# Sheet_Power.net
KiCad netlist of a schematic drawn in Altium Designer
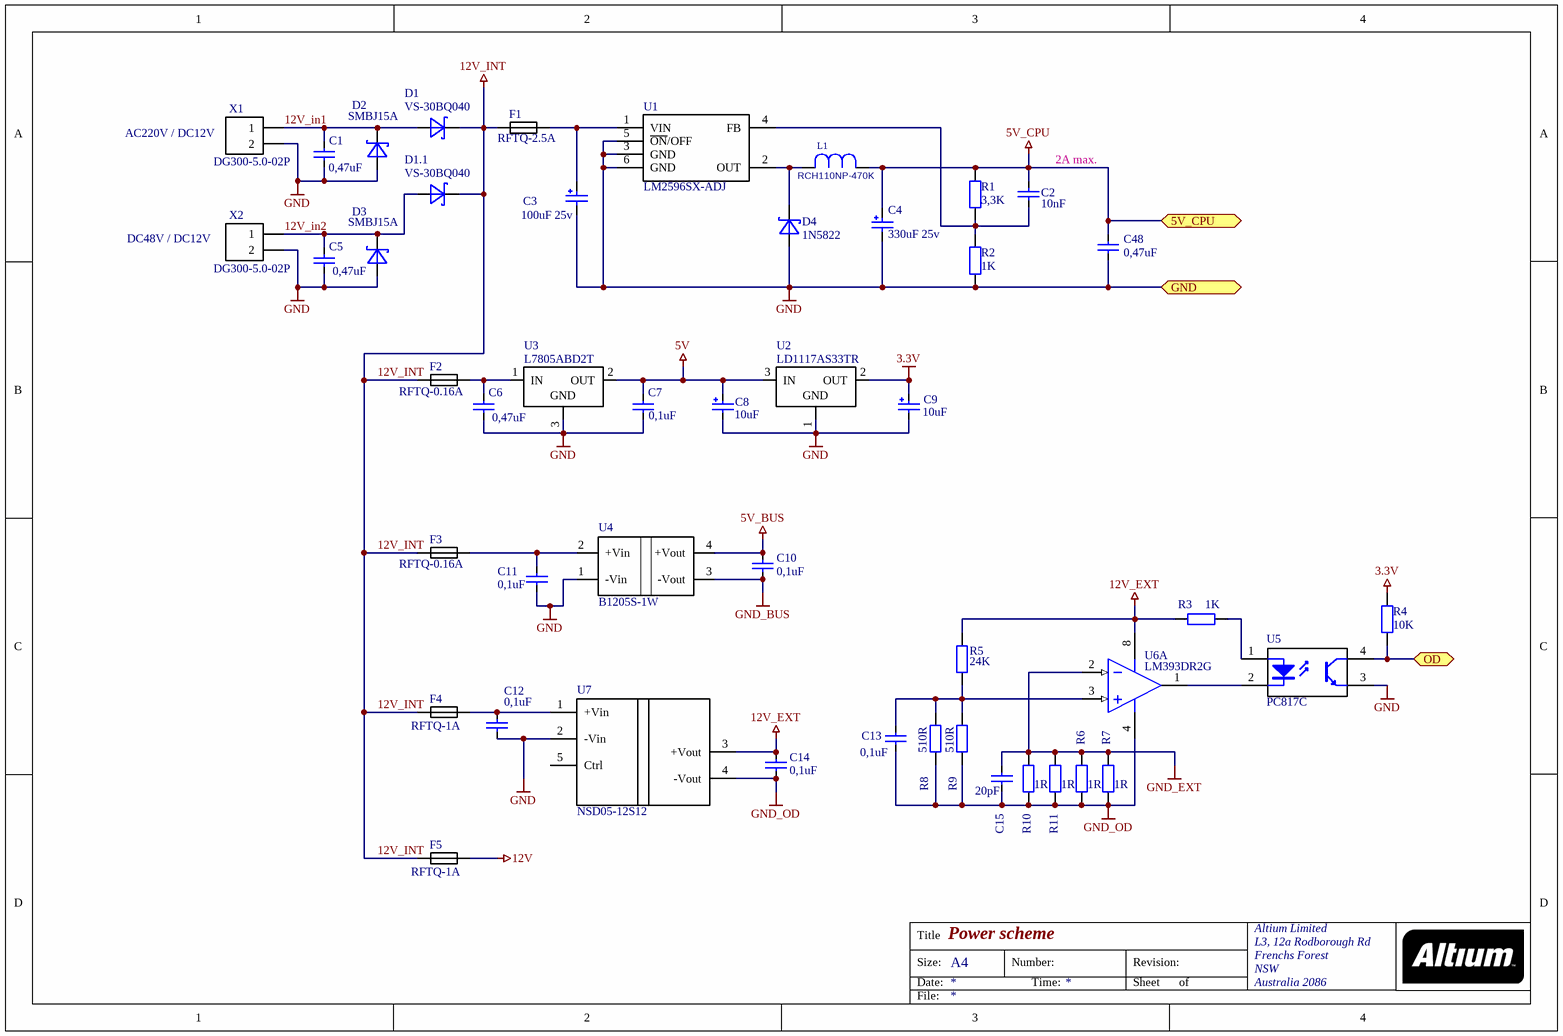
[diagram p0: Sheet_Power.SchDoc]

(export (version "E")
  (design (tool "Eeschema 10.0.6"))
  (components
    (comp (ref "C1")
      (value "0,47uF")
      (footprint "C_1206")
      (description "Capacitor semi")
      (fields (field (name "Comment") "Cap_Semi"))
      (libsource (lib "Capacitor") (part "Cap_Semi"))
    )
    (comp (ref "C2")
      (value "10nF")
      (footprint "C_0805")
      (description "Capacitor semi")
      (fields (field (name "Comment") "Cap_Semi"))
      (libsource (lib "Capacitor") (part "Cap_Semi"))
    )
    (comp (ref "C3")
      (value "100uF 25v")
      (footprint "8x11")
      (description "Capacitor Polar")
      (fields (field (name "Comment") "Cap_Polar"))
      (libsource (lib "Capacitor") (part "Cap_Polar"))
    )
    (comp (ref "C4")
      (value "330uF 25v")
      (footprint "10x16")
      (description "Capacitor Polar")
      (fields (field (name "Comment") "Cap_Polar"))
      (libsource (lib "Capacitor") (part "Cap_Polar"))
    )
    (comp (ref "C5")
      (value "0,47uF")
      (footprint "C_1206")
      (description "Capacitor semi")
      (fields (field (name "Comment") "Cap_Semi"))
      (libsource (lib "Capacitor") (part "Cap_Semi"))
    )
    (comp (ref "C6")
      (value "0,47uF")
      (footprint "C_1206")
      (description "Capacitor semi")
      (fields (field (name "Comment") "Cap_Semi"))
      (libsource (lib "Capacitor") (part "Cap_Semi"))
    )
    (comp (ref "C7")
      (value "0,1uF")
      (footprint "C_0805")
      (description "Capacitor semi")
      (fields (field (name "Comment") "Cap_Semi"))
      (libsource (lib "Capacitor") (part "Cap_Semi"))
    )
    (comp (ref "C8")
      (value "10uF")
      (footprint "5x11")
      (description "Capacitor polar")
      (fields (field (name "Comment") "Cap_Polar"))
      (libsource (lib "Capacitor") (part "Capacitor Polar"))
    )
    (comp (ref "C9")
      (value "10uF")
      (footprint "5x11")
      (description "Capacitor polar")
      (fields (field (name "Comment") "Cap_Polar"))
      (libsource (lib "Capacitor") (part "Capacitor Polar"))
    )
    (comp (ref "C10")
      (value "0,1uF")
      (footprint "C_0805")
      (description "Capacitor semi")
      (fields (field (name "Comment") "Cap_Semi"))
      (libsource (lib "Capacitor") (part "Cap_Semi"))
    )
    (comp (ref "C11")
      (value "0,1uF")
      (footprint "C_0805")
      (description "Capacitor semi")
      (fields (field (name "Comment") "Cap_Semi"))
      (libsource (lib "Capacitor") (part "Cap_Semi"))
    )
    (comp (ref "C12")
      (value "0,1uF")
      (footprint "C_0805")
      (description "Capacitor semi")
      (fields (field (name "Comment") "Cap_Semi"))
      (libsource (lib "Capacitor") (part "Cap_Semi"))
    )
    (comp (ref "C13")
      (value "0,1uF")
      (footprint "C_0805")
      (description "Capacitor semi")
      (fields (field (name "Comment") "Cap_Semi"))
      (libsource (lib "Capacitor") (part "Cap_Semi"))
    )
    (comp (ref "C14")
      (value "0,1uF")
      (footprint "C_0805")
      (description "Capacitor semi")
      (fields (field (name "Comment") "Cap_Semi"))
      (libsource (lib "Capacitor") (part "Cap_Semi"))
    )
    (comp (ref "C15")
      (value "20pF")
      (footprint "C_0805")
      (description "Capacitor semi")
      (fields (field (name "Comment") "Cap_Semi"))
      (libsource (lib "Capacitor") (part "Cap_Semi"))
    )
    (comp (ref "C48")
      (value "0,47uF")
      (footprint "C_1206")
      (description "Capacitor semi")
      (fields (field (name "Comment") "Cap_Semi"))
      (libsource (lib "Capacitor") (part "Cap_Semi"))
    )
    (comp (ref "D1")
      (value "VS-30BQ040")
      (footprint "SMC")
      (description "Diode Schottky")
      (libsource (lib "Diode") (part "VS-30BQ040"))
    )
    (comp (ref "D1.1")
      (value "VS-30BQ040")
      (footprint "SMC")
      (description "Diode Schottky")
      (libsource (lib "Diode") (part "VS-30BQ040"))
    )
    (comp (ref "D2")
      (value "SMBJ15A")
      (footprint "SMB")
      (description "Supressor")
      (libsource (lib "Diode") (part "SMBJ13A"))
    )
    (comp (ref "D3")
      (value "SMBJ15A")
      (footprint "SMB")
      (description "Supressor")
      (libsource (lib "Diode") (part "SMBJ13A"))
    )
    (comp (ref "D4")
      (value "1N5822")
      (footprint "DO-201")
      (description "Diode Schottky")
      (libsource (lib "Diode") (part "1N5822"))
    )
    (comp (ref "F1")
      (value "RFTQ-2.5A")
      (footprint "Fuse RFTQ")
      (description "Fuse")
      (libsource (lib "Other") (part "Fuse"))
    )
    (comp (ref "F2")
      (value "RFTQ-0.16A")
      (footprint "Fuse RFTQ")
      (description "Fuse")
      (libsource (lib "Other") (part "Fuse"))
    )
    (comp (ref "F3")
      (value "RFTQ-0.16A")
      (footprint "Fuse RFTQ")
      (description "Fuse")
      (libsource (lib "Other") (part "Fuse"))
    )
    (comp (ref "F4")
      (value "RFTQ-1A")
      (footprint "Fuse RFTQ")
      (description "Fuse")
      (libsource (lib "Other") (part "Fuse"))
    )
    (comp (ref "F5")
      (value "RFTQ-1A")
      (footprint "Fuse RFTQ")
      (description "Fuse")
      (libsource (lib "Other") (part "Fuse"))
    )
    (comp (ref "L1")
      (value "RCH110NP-470K")
      (footprint "RCH-110")
      (description "Inductor")
      (libsource (lib "Induction") (part "Inductor"))
    )
    (comp (ref "R1")
      (value "3,3K")
      (footprint "R_0805")
      (description "Resistor")
      (libsource (lib "") (part "Resistor_1"))
    )
    (comp (ref "R2")
      (value "1K")
      (footprint "R_0805")
      (description "Resistor")
      (libsource (lib "") (part "Resistor_1"))
    )
    (comp (ref "R3")
      (value "1K")
      (footprint "R_0805")
      (description "Resistor")
      (libsource (lib "Resistors") (part "Resistor"))
    )
    (comp (ref "R4")
      (value "10K")
      (footprint "R_0805")
      (description "Resistor")
      (libsource (lib "") (part "Resistor_1"))
    )
    (comp (ref "R5")
      (value "24K")
      (footprint "R_0805")
      (description "Resistor")
      (libsource (lib "") (part "Resistor_1"))
    )
    (comp (ref "R6")
      (value "1R")
      (footprint "R_1206")
      (description "Resistor")
      (libsource (lib "") (part "Resistor_1"))
    )
    (comp (ref "R7")
      (value "1R")
      (footprint "R_1206")
      (description "Resistor")
      (libsource (lib "") (part "Resistor_1"))
    )
    (comp (ref "R8")
      (value "510R")
      (footprint "R_0805")
      (description "Resistor")
      (libsource (lib "") (part "Resistor_1"))
    )
    (comp (ref "R9")
      (value "510R")
      (footprint "R_0805")
      (description "Resistor")
      (libsource (lib "") (part "Resistor_1"))
    )
    (comp (ref "R10")
      (value "1R")
      (footprint "R_1206")
      (description "Resistor")
      (libsource (lib "") (part "Resistor_1"))
    )
    (comp (ref "R11")
      (value "1R")
      (footprint "R_1206")
      (description "Resistor")
      (libsource (lib "") (part "Resistor_1"))
    )
    (comp (ref "U1")
      (value "LM2596SX-ADJ")
      (footprint "D2PAK_5p")
      (description "Easy Switcher 3.0A Step-Down Voltage Regulator")
      (libsource (lib "Power") (part "LM2596SX-ADJ"))
    )
    (comp (ref "U2")
      (value "LD1117AS33TR")
      (footprint "SOT-223_N")
      (description "Voltage Regulators 800mA")
      (libsource (lib "Power") (part "LD1117AS33TR"))
    )
    (comp (ref "U3")
      (value "L7805ABD2T")
      (footprint "D2PAK_3p")
      (description "Voltage Regulators")
      (libsource (lib "Power") (part "L7805ABD2T"))
    )
    (comp (ref "U4")
      (value "B1205S-1W")
      (footprint "SIP4")
      (description "DC/DC converter")
      (libsource (lib "Power") (part "B0505S-1W"))
    )
    (comp (ref "U5")
      (value "PC817C")
      (footprint "DIP-4")
      (description "Optocoupler")
      (libsource (lib "Chip_Packaging") (part "PC817"))
    )
    (comp (ref "U6")
      (value "LM393DR2G")
      (footprint "SO-8_L")
      (description "Dual Comparators")
      (libsource (lib "Chip_Packaging") (part "LM393DR2G"))
    )
    (comp (ref "U7")
      (value "NSD05-12S12")
      (footprint "NSD05")
      (description "DC/DC Regulated Single Output")
      (libsource (lib "Power") (part "NSD05-12S12"))
    )
    (comp (ref "X1")
      (value "DG300-5.0-02P")
      (footprint "5mm 2")
      (description "Connector 5mm")
      (fields (field (name "ALTIUM_UNNAMED_1") "DG300-5.0-02P"))
      (libsource (lib "Connect") (part "DG300_2pin"))
    )
    (comp (ref "X2")
      (value "DG300-5.0-02P")
      (footprint "5mm 2")
      (description "Connector 5mm")
      (fields (field (name "ALTIUM_UNNAMED_1") "DG300-5.0-02P"))
      (libsource (lib "Connect") (part "DG300_2pin"))
    )
  )
  (nets
    (net (code "1") (name "/12V_in1") (class "Default")
      (node (ref "C1") (pin "2") (pinfunction "2_2") (pintype "passive"))
      (node (ref "D1") (pin "1") (pinfunction "A_1") (pintype "passive"))
      (node (ref "D2") (pin "2") (pinfunction "C_2") (pintype "passive"))
      (node (ref "X1") (pin "1") (pinfunction "1_1") (pintype "passive"))
    )
    (net (code "2") (name "/12V_in2") (class "Default")
      (node (ref "C5") (pin "2") (pinfunction "2_2") (pintype "passive"))
      (node (ref "D1.1") (pin "1") (pinfunction "A_1") (pintype "passive"))
      (node (ref "D3") (pin "2") (pinfunction "C_2") (pintype "passive"))
      (node (ref "X2") (pin "1") (pinfunction "1_1") (pintype "passive"))
    )
    (net (code "3") (name "/OD") (class "Default")
      (node (ref "R4") (pin "1") (pinfunction "1_1") (pintype "passive"))
      (node (ref "U5") (pin "4") (pinfunction "C_4") (pintype "passive"))
    )
    (net (code "4") (name "3.3V") (class "Default")
      (node (ref "C9") (pin "1") (pinfunction "1_1") (pintype "passive"))
      (node (ref "R4") (pin "2") (pinfunction "2_2") (pintype "passive"))
      (node (ref "U2") (pin "2") (pinfunction "OUT_2") (pintype "power_in"))
    )
    (net (code "5") (name "5V") (class "Default")
      (node (ref "C7") (pin "2") (pinfunction "2_2") (pintype "passive"))
      (node (ref "C8") (pin "1") (pinfunction "1_1") (pintype "passive"))
      (node (ref "U2") (pin "3") (pinfunction "IN_3") (pintype "power_in"))
      (node (ref "U3") (pin "2") (pinfunction "OUT_2") (pintype "power_in"))
    )
    (net (code "6") (name "5V_BUS") (class "Default")
      (node (ref "C10") (pin "1") (pinfunction "1_1") (pintype "passive"))
      (node (ref "U4") (pin "4") (pinfunction "+Vout_4") (pintype "power_in"))
    )
    (net (code "7") (name "5V_CPU") (class "Default")
      (node (ref "C2") (pin "1") (pinfunction "1_1") (pintype "passive"))
      (node (ref "C4") (pin "1") (pinfunction "1_1") (pintype "passive"))
      (node (ref "C48") (pin "2") (pinfunction "2_2") (pintype "passive"))
      (node (ref "L1") (pin "1") (pintype "passive"))
      (node (ref "R1") (pin "2") (pinfunction "2_2") (pintype "passive"))
    )
    (net (code "8") (name "12V") (class "Default") (node (ref "F5") (pin "1") (pintype "passive")))
    (net (code "9") (name "12V_EXT") (class "Default")
      (node (ref "C14") (pin "2") (pinfunction "2_2") (pintype "passive"))
      (node (ref "R3") (pin "1") (pinfunction "1_1") (pintype "passive"))
      (node (ref "R5") (pin "2") (pinfunction "2_2") (pintype "passive"))
      (node (ref "U6") (pin "8") (pinfunction "VCC_8") (pintype "power_in"))
      (node (ref "U7") (pin "3") (pinfunction "+Vout_3") (pintype "power_in"))
    )
    (net (code "10") (name "12V_INT") (class "Default")
      (node (ref "D1") (pin "2") (pinfunction "C_2") (pintype "passive"))
      (node (ref "D1.1") (pin "2") (pinfunction "C_2") (pintype "passive"))
      (node (ref "F1") (pin "2") (pintype "passive"))
      (node (ref "F2") (pin "2") (pintype "passive"))
      (node (ref "F3") (pin "2") (pintype "passive"))
      (node (ref "F4") (pin "2") (pintype "passive"))
      (node (ref "F5") (pin "2") (pintype "passive"))
    )
    (net (code "11") (name "GND") (class "Default")
      (node (ref "C1") (pin "1") (pinfunction "1_1") (pintype "passive"))
      (node (ref "C11") (pin "2") (pinfunction "2_2") (pintype "passive"))
      (node (ref "C12") (pin "1") (pinfunction "1_1") (pintype "passive"))
      (node (ref "C3") (pin "2") (pinfunction "2_2") (pintype "passive"))
      (node (ref "C4") (pin "2") (pinfunction "2_2") (pintype "passive"))
      (node (ref "C48") (pin "1") (pinfunction "1_1") (pintype "passive"))
      (node (ref "C5") (pin "1") (pinfunction "1_1") (pintype "passive"))
      (node (ref "C6") (pin "1") (pinfunction "1_1") (pintype "passive"))
      (node (ref "C7") (pin "1") (pinfunction "1_1") (pintype "passive"))
      (node (ref "C8") (pin "2") (pinfunction "2_2") (pintype "passive"))
      (node (ref "C9") (pin "2") (pinfunction "2_2") (pintype "passive"))
      (node (ref "D2") (pin "1") (pinfunction "A_1") (pintype "passive"))
      (node (ref "D3") (pin "1") (pinfunction "A_1") (pintype "passive"))
      (node (ref "D4") (pin "1") (pinfunction "A_1") (pintype "passive"))
      (node (ref "R2") (pin "1") (pinfunction "1_1") (pintype "passive"))
      (node (ref "U1") (pin "3") (pinfunction "GND_3") (pintype "power_in"))
      (node (ref "U1") (pin "5") (pinfunction "~{ON}/OFF_5") (pintype "passive"))
      (node (ref "U1") (pin "6") (pinfunction "GND_6") (pintype "power_in"))
      (node (ref "U2") (pin "1") (pinfunction "GND_1") (pintype "power_in"))
      (node (ref "U3") (pin "3") (pinfunction "GND_3") (pintype "power_in"))
      (node (ref "U4") (pin "1") (pinfunction "-Vin_1") (pintype "power_in"))
      (node (ref "U5") (pin "3") (pinfunction "E_3") (pintype "passive"))
      (node (ref "U7") (pin "2") (pinfunction "-Vin_2") (pintype "power_in"))
      (node (ref "X1") (pin "2") (pinfunction "2_2") (pintype "passive"))
      (node (ref "X2") (pin "2") (pinfunction "2_2") (pintype "passive"))
    )
    (net (code "12") (name "GND_BUS") (class "Default")
      (node (ref "C10") (pin "2") (pinfunction "2_2") (pintype "passive"))
      (node (ref "U4") (pin "3") (pinfunction "-Vout_3") (pintype "power_in"))
    )
    (net (code "13") (name "GND_EXT") (class "Default")
      (node (ref "C15") (pin "2") (pinfunction "2_2") (pintype "passive"))
      (node (ref "R10") (pin "2") (pinfunction "2_2") (pintype "passive"))
      (node (ref "R11") (pin "2") (pinfunction "2_2") (pintype "passive"))
      (node (ref "R6") (pin "2") (pinfunction "2_2") (pintype "passive"))
      (node (ref "R7") (pin "2") (pinfunction "2_2") (pintype "passive"))
      (node (ref "U6") (pin "2") (pinfunction "INA-_2") (pintype "input"))
    )
    (net (code "14") (name "GND_OD") (class "Default")
      (node (ref "C13") (pin "1") (pinfunction "1_1") (pintype "passive"))
      (node (ref "C14") (pin "1") (pinfunction "1_1") (pintype "passive"))
      (node (ref "C15") (pin "1") (pinfunction "1_1") (pintype "passive"))
      (node (ref "R10") (pin "1") (pinfunction "1_1") (pintype "passive"))
      (node (ref "R11") (pin "1") (pinfunction "1_1") (pintype "passive"))
      (node (ref "R6") (pin "1") (pinfunction "1_1") (pintype "passive"))
      (node (ref "R7") (pin "1") (pinfunction "1_1") (pintype "passive"))
      (node (ref "R8") (pin "1") (pinfunction "1_1") (pintype "passive"))
      (node (ref "R9") (pin "1") (pinfunction "1_1") (pintype "passive"))
      (node (ref "U6") (pin "4") (pinfunction "GND_4") (pintype "power_in"))
      (node (ref "U7") (pin "4") (pinfunction "-Vout_4") (pintype "power_in"))
    )
    (net (code "15") (name "Net-(D4-C)") (class "Default")
      (node (ref "D4") (pin "2") (pinfunction "C_2") (pintype "passive"))
      (node (ref "L1") (pin "2") (pintype "passive"))
      (node (ref "U1") (pin "2") (pinfunction "OUT_2") (pintype "open_emitter"))
    )
    (net (code "16") (name "Net-(U1-FB)") (class "Default")
      (node (ref "C2") (pin "2") (pinfunction "2_2") (pintype "passive"))
      (node (ref "R1") (pin "1") (pinfunction "1_1") (pintype "passive"))
      (node (ref "R2") (pin "2") (pinfunction "2_2") (pintype "passive"))
      (node (ref "U1") (pin "4") (pinfunction "FB_4") (pintype "passive"))
    )
    (net (code "17") (name "Net-(U1-VIN)") (class "Default")
      (node (ref "C3") (pin "1") (pinfunction "1_1") (pintype "passive"))
      (node (ref "F1") (pin "1") (pintype "passive"))
      (node (ref "U1") (pin "1") (pinfunction "VIN_1") (pintype "power_in"))
    )
    (net (code "18") (name "Net-(U3-IN)") (class "Default")
      (node (ref "C6") (pin "2") (pinfunction "2_2") (pintype "passive"))
      (node (ref "F2") (pin "1") (pintype "passive"))
      (node (ref "U3") (pin "1") (pinfunction "IN_1") (pintype "power_in"))
    )
    (net (code "19") (name "Net-(U4-+Vin)") (class "Default")
      (node (ref "C11") (pin "1") (pinfunction "1_1") (pintype "passive"))
      (node (ref "F3") (pin "1") (pintype "passive"))
      (node (ref "U4") (pin "2") (pinfunction "+Vin_2") (pintype "power_in"))
    )
    (net (code "20") (name "Net-(U5-A)") (class "Default")
      (node (ref "R3") (pin "2") (pinfunction "2_2") (pintype "passive"))
      (node (ref "U5") (pin "1") (pinfunction "A_1") (pintype "passive"))
    )
    (net (code "21") (name "Net-(U5-K)") (class "Default")
      (node (ref "U5") (pin "2") (pinfunction "K_2") (pintype "passive"))
      (node (ref "U6") (pin "1") (pinfunction "OUTA_1") (pintype "open_collector"))
    )
    (net (code "22") (name "Net-(U6A-INA+)") (class "Default")
      (node (ref "C13") (pin "2") (pinfunction "2_2") (pintype "passive"))
      (node (ref "R5") (pin "1") (pinfunction "1_1") (pintype "passive"))
      (node (ref "R8") (pin "2") (pinfunction "2_2") (pintype "passive"))
      (node (ref "R9") (pin "2") (pinfunction "2_2") (pintype "passive"))
      (node (ref "U6") (pin "3") (pinfunction "INA+_3") (pintype "input"))
    )
    (net (code "23") (name "Net-(U7-+Vin)") (class "Default")
      (node (ref "C12") (pin "2") (pinfunction "2_2") (pintype "passive"))
      (node (ref "F4") (pin "1") (pintype "passive"))
      (node (ref "U7") (pin "1") (pinfunction "+Vin_1") (pintype "power_in"))
    )
    (net (code "24") (name "unconnected-(U7-Ctrl-Pad5)") (class "Default")
      (node (ref "U7") (pin "5") (pinfunction "Ctrl_5") (pintype "passive"))
    )
  )
)
